# EasyEDA_ChisFlash_V0_1_Pichu.net
KiCad netlist of a schematic drawn in EasyEDA Pro
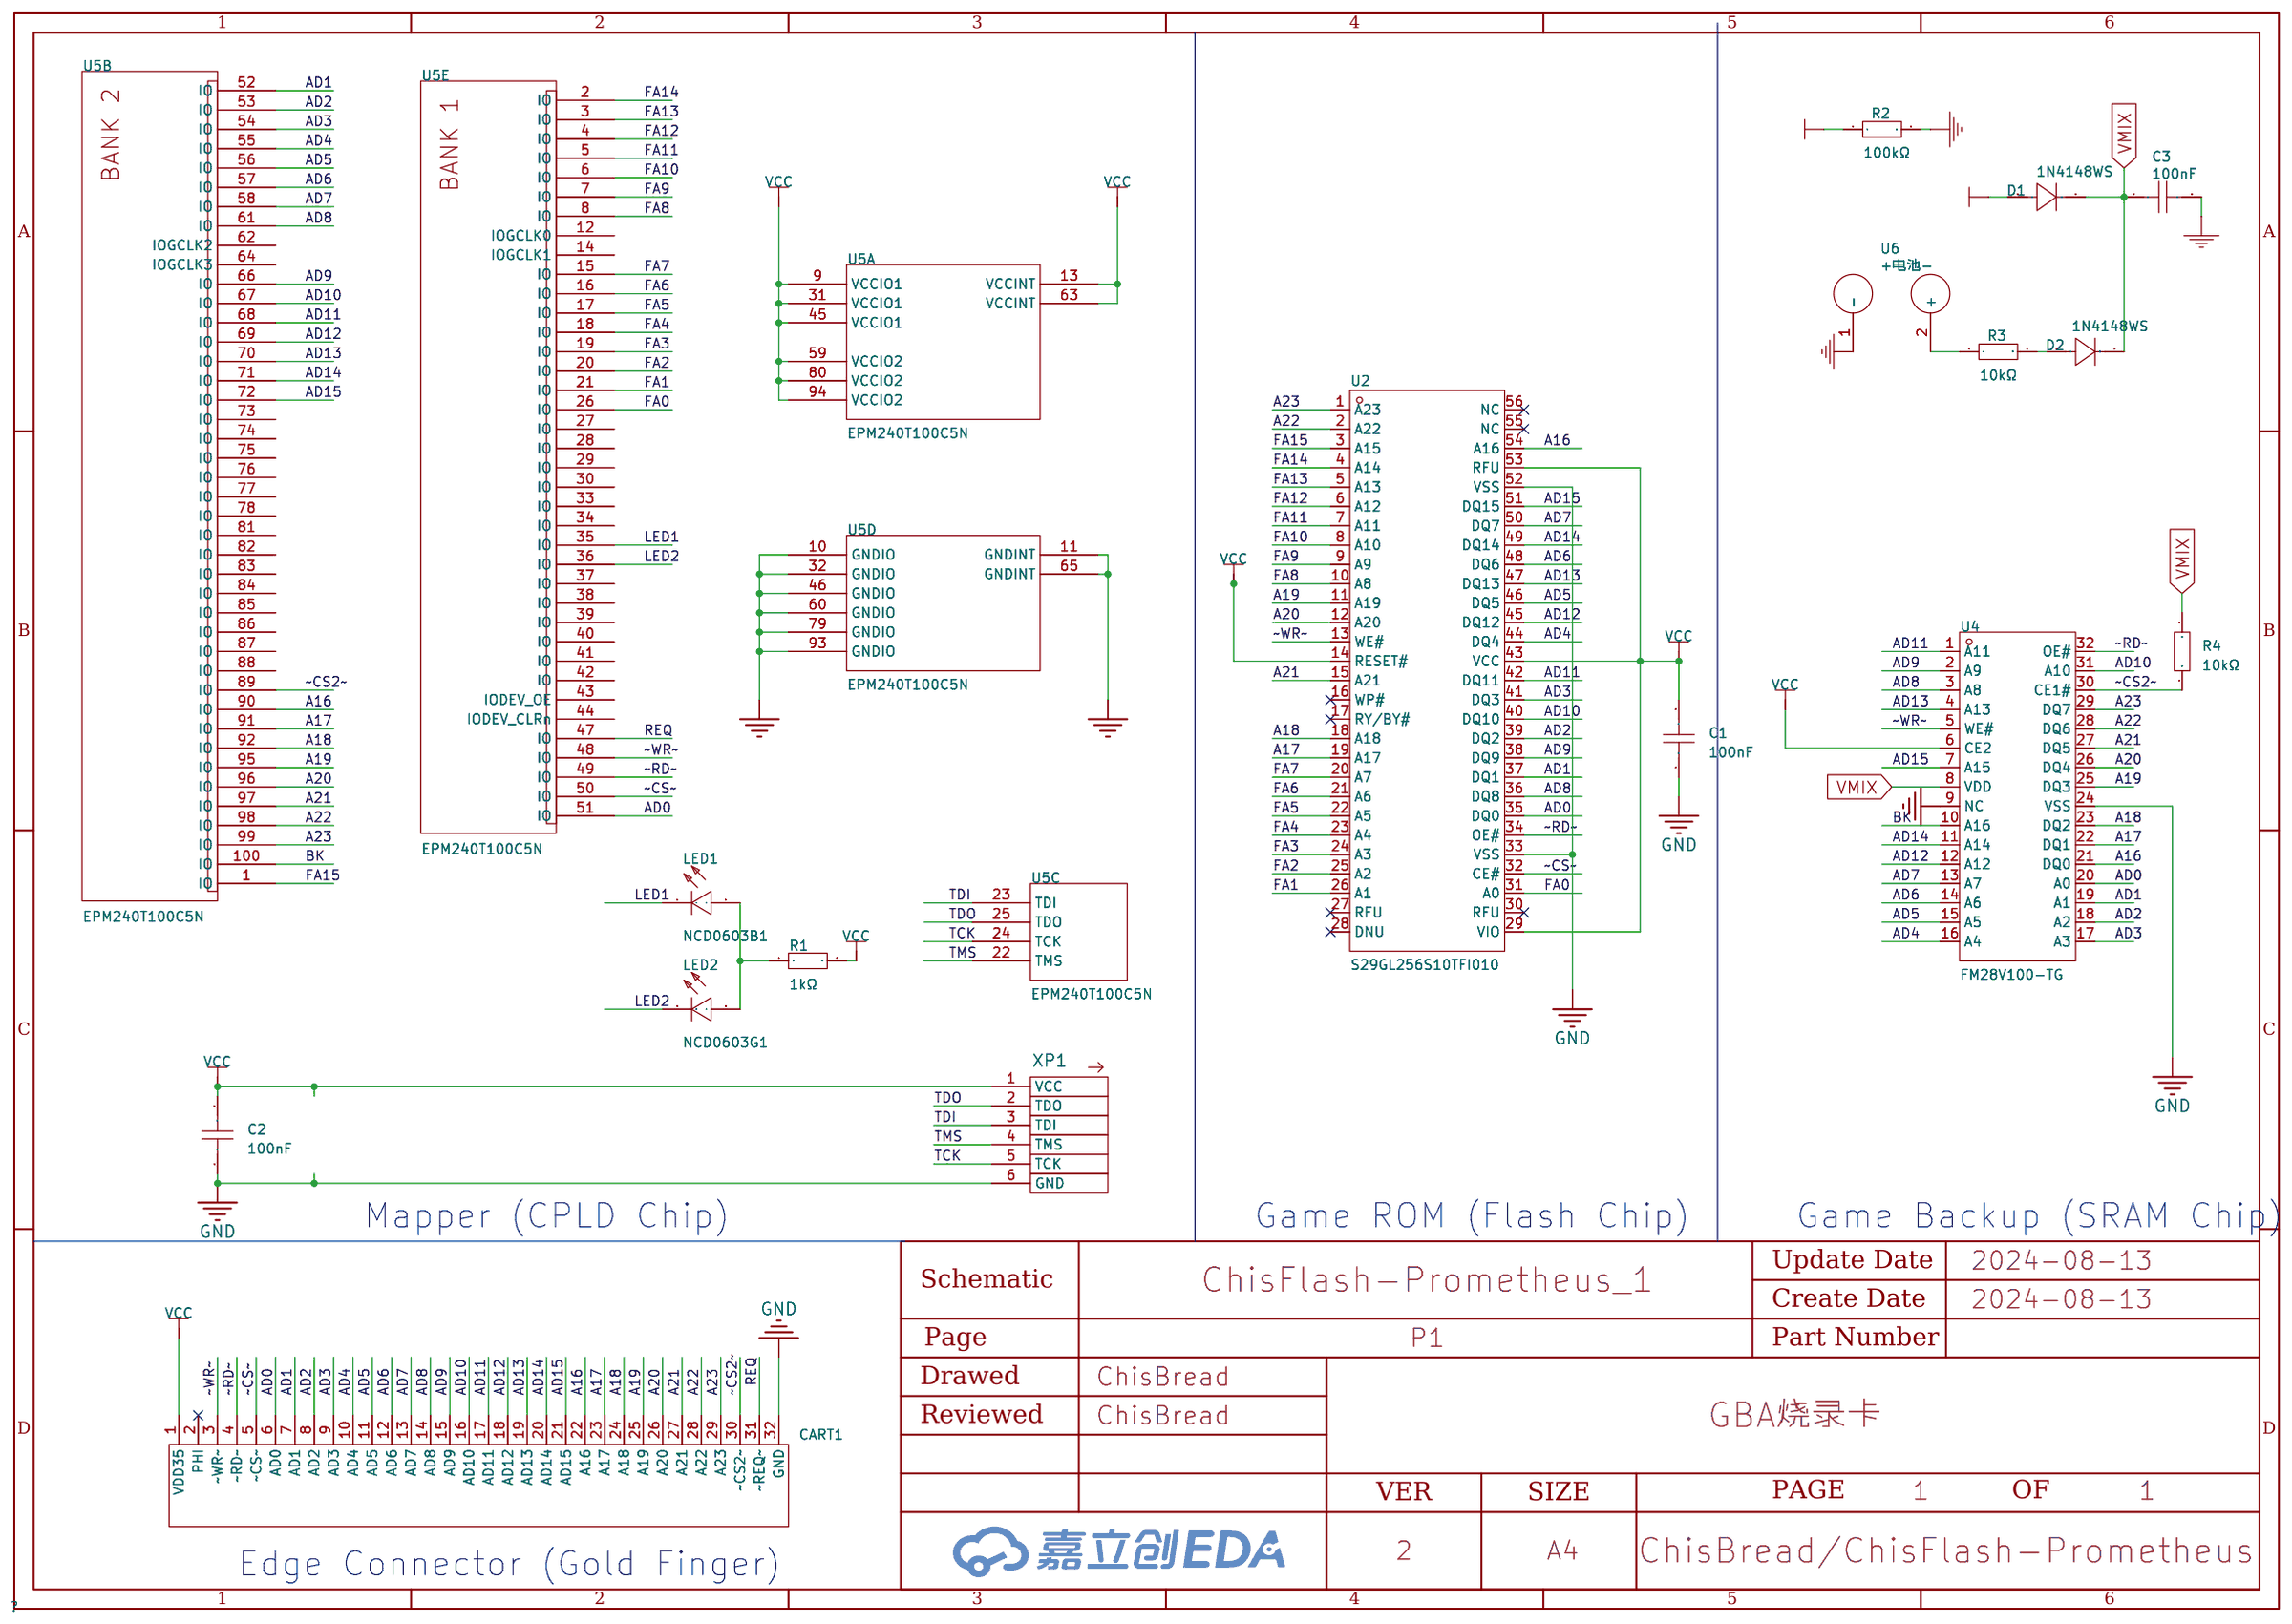
[diagram p0: schematic sheet]

(export (version "E")
  (design (tool "Eeschema 10.0.6"))
  (components
    (comp (ref "C1")
      (value "100nF")
      (footprint "easyedapro:C0603")
      (libsource (lib "easyedapro") (part "CapAcitance"))
    )
    (comp (ref "C2")
      (value "100nF")
      (footprint "easyedapro:C0603")
      (libsource (lib "easyedapro") (part "CapAcitance"))
    )
    (comp (ref "C3")
      (value "100nF")
      (footprint "easyedapro:C0603")
      (description "容值:100nF;精度:±10%;额定电压:50V;材质(温度系数):X7R;")
      (fields
        (field (name "Manufacturer Part") "CGA0603X7R104K500JT")
        (field (name "Manufacturer") "HRE(芯声)")
      )
      (libsource (lib "easyedapro") (part "CGA0603X7R104K500JT"))
    )
    (comp (ref "CART1")
      (value "~")
      (footprint "easyedapro:GBACartridge")
      (description "GBA Cartridge")
      (libsource (lib "easyedapro") (part "GBACartridge"))
    )
    (comp (ref "D1")
      (value "1N4148WS")
      (footprint "easyedapro:SOD-323_L1.8-W1.3-LS2.5-RD")
      (description "二极管配置:独立式;正向压降(Vf):1.25V@150mA;直流反向耐压(Vr):100V;平均整流电流(Io):300mA;功率:400mW;反向恢复时间(trr):8ns;")
      (fields (field (name "Manufacturer") "JSMSEMI(杰盛微)"))
      (libsource (lib "easyedapro") (part "1N4148WS_C917117"))
    )
    (comp (ref "D2")
      (value "1N4148WS")
      (footprint "easyedapro:SOD-323_L1.8-W1.3-LS2.5-RD")
      (description "二极管配置:独立式;正向压降(Vf):1.25V@150mA;直流反向耐压(Vr):100V;平均整流电流(Io):300mA;功率:400mW;反向恢复时间(trr):8ns;")
      (fields (field (name "Manufacturer") "JSMSEMI(杰盛微)"))
      (libsource (lib "easyedapro") (part "1N4148WS_C917117"))
    )
    (comp (ref "LED1")
      (value "NCD0603B1")
      (footprint "easyedapro:LED0603-RD")
      (fields (field (name "Manufacturer") "国星光电"))
      (libsource (lib "easyedapro") (part "FC-DA1608BK-470H10"))
    )
    (comp (ref "LED2")
      (value "NCD0603G1")
      (footprint "easyedapro:LED0603-RD")
      (fields (field (name "Manufacturer") "国星光电"))
      (libsource (lib "easyedapro") (part "FC-D1608UGK-520D10"))
    )
    (comp (ref "R1")
      (value "1kΩ")
      (footprint "easyedapro:R0603")
      (description "电阻类型:厚膜电阻;阻值:1kΩ;精度:±1%;功率:100mW;最大工作电压:75V;温度系数:±100ppm/°C;")
      (fields
        (field (name "Manufacturer Part") "0603WAF1001T5E")
        (field (name "Manufacturer") "UNI-ROYAL(厚声)")
      )
      (libsource (lib "easyedapro") (part "0603WAF1001T5E"))
    )
    (comp (ref "R2")
      (value "100kΩ")
      (footprint "easyedapro:R0603")
      (description "电阻类型:厚膜电阻;阻值:100kΩ;精度:±1%;功率:100mW;最大工作电压:75V;温度系数:±100ppm/°C;")
      (fields
        (field (name "Manufacturer Part") "0603WAF1003T5E")
        (field (name "Manufacturer") "UNI-ROYAL(厚声)")
      )
      (libsource (lib "easyedapro") (part "0603WAF1003T5E"))
    )
    (comp (ref "R3")
      (value "10kΩ")
      (footprint "easyedapro:R0603")
      (description "电阻类型:厚膜电阻;阻值:10kΩ;精度:±1%;功率:100mW;最大工作电压:75V;温度系数:±100ppm/°C;")
      (fields
        (field (name "Manufacturer Part") "0603WAF1002T5E")
        (field (name "Manufacturer") "UNI-ROYAL(厚声)")
      )
      (libsource (lib "easyedapro") (part "0603WAF1002T5E"))
    )
    (comp (ref "R4")
      (value "10kΩ")
      (footprint "easyedapro:R0603")
      (description "电阻类型:厚膜电阻;阻值:10kΩ;精度:±1%;功率:100mW;最大工作电压:75V;温度系数:±100ppm/°C;")
      (fields
        (field (name "Manufacturer Part") "0603WAF1002T5E")
        (field (name "Manufacturer") "UNI-ROYAL(厚声)")
      )
      (libsource (lib "easyedapro") (part "0603WAF1002T5E"))
    )
    (comp (ref "U2")
      (value "S29GL256S10TFI010")
      (footprint "easyedapro:TSOP-56_L18.4-W14.0-P0.50-LS20.0-TL")
      (fields (field (name "Manufacturer") "SPANSION(飞索)"))
      (libsource (lib "easyedapro") (part "S29GL256S10TFI010"))
    )
    (comp (ref "U4")
      (value "FM28V100-TG")
      (fields (field (name "Manufacturer") "CYPRESS(赛普拉斯)"))
      (libsource (lib "easyedapro") (part "FM28V100-TG_C2959453"))
    )
    (comp (ref "U5")
      (value "EPM240T100C5N")
      (footprint "easyedapro:TQFP-100_L14.0-W14.0-P0.50-LS16.0-BL")
      (description "类型:其它PLD;逻辑门数量:-;逻辑单元数:-;逻辑阵列块数:240;")
      (fields (field (name "Manufacturer") "Intel/Altera"))
      (libsource (lib "easyedapro") (part "EPM240T100C5N"))
    )
    (comp (ref "U6") (value "+电池-") (footprint "easyedapro:电池") (libsource (lib "easyedapro") (part "+电池-")))
    (comp (ref "XP1")
      (value "JTAG")
      (footprint "easyedapro:HDR-TH_6P-P1.27-V-M-1")
      (libsource (lib "easyedapro") (part "jtag"))
    )
  )
  (nets
    (net (code "1") (name "/A16") (class "Default")
      (node (ref "CART1") (pin "22") (pinfunction "A16_22") (pintype "input"))
      (node (ref "U2") (pin "54") (pinfunction "A16_54") (pintype "input"))
      (node (ref "U4") (pin "21") (pinfunction "DQ0_21") (pintype "unspecified"))
      (node (ref "U5") (pin "90") (pinfunction "IO_90") (pintype "bidirectional"))
    )
    (net (code "2") (name "/A17") (class "Default")
      (node (ref "CART1") (pin "23") (pinfunction "A17_23") (pintype "input"))
      (node (ref "U2") (pin "19") (pinfunction "A17_19") (pintype "input"))
      (node (ref "U4") (pin "22") (pinfunction "DQ1_22") (pintype "unspecified"))
      (node (ref "U5") (pin "91") (pinfunction "IO_91") (pintype "bidirectional"))
    )
    (net (code "3") (name "/A18") (class "Default")
      (node (ref "CART1") (pin "24") (pinfunction "A18_24") (pintype "input"))
      (node (ref "U2") (pin "18") (pinfunction "A18_18") (pintype "input"))
      (node (ref "U4") (pin "23") (pinfunction "DQ2_23") (pintype "unspecified"))
      (node (ref "U5") (pin "92") (pinfunction "IO_92") (pintype "bidirectional"))
    )
    (net (code "4") (name "/A19") (class "Default")
      (node (ref "CART1") (pin "25") (pinfunction "A19_25") (pintype "input"))
      (node (ref "U2") (pin "11") (pinfunction "A19_11") (pintype "input"))
      (node (ref "U4") (pin "25") (pinfunction "DQ3_25") (pintype "unspecified"))
      (node (ref "U5") (pin "95") (pinfunction "IO_95") (pintype "bidirectional"))
    )
    (net (code "5") (name "/A20") (class "Default")
      (node (ref "CART1") (pin "26") (pinfunction "A20_26") (pintype "input"))
      (node (ref "U2") (pin "12") (pinfunction "A20_12") (pintype "input"))
      (node (ref "U4") (pin "26") (pinfunction "DQ4_26") (pintype "unspecified"))
      (node (ref "U5") (pin "96") (pinfunction "IO_96") (pintype "bidirectional"))
    )
    (net (code "6") (name "/A21") (class "Default")
      (node (ref "CART1") (pin "27") (pinfunction "A21_27") (pintype "input"))
      (node (ref "U2") (pin "15") (pinfunction "A21_15") (pintype "input"))
      (node (ref "U4") (pin "27") (pinfunction "DQ5_27") (pintype "unspecified"))
      (node (ref "U5") (pin "97") (pinfunction "IO_97") (pintype "bidirectional"))
    )
    (net (code "7") (name "/A22") (class "Default")
      (node (ref "CART1") (pin "28") (pinfunction "A22_28") (pintype "input"))
      (node (ref "U2") (pin "2") (pinfunction "A22_2") (pintype "input"))
      (node (ref "U4") (pin "28") (pinfunction "DQ6_28") (pintype "unspecified"))
      (node (ref "U5") (pin "98") (pinfunction "IO_98") (pintype "bidirectional"))
    )
    (net (code "8") (name "/A23") (class "Default")
      (node (ref "CART1") (pin "29") (pinfunction "A23_29") (pintype "input"))
      (node (ref "U2") (pin "1") (pinfunction "A23_1") (pintype "input"))
      (node (ref "U4") (pin "29") (pinfunction "DQ7_29") (pintype "unspecified"))
      (node (ref "U5") (pin "99") (pinfunction "IO_99") (pintype "bidirectional"))
    )
    (net (code "9") (name "/AD0") (class "Default")
      (node (ref "CART1") (pin "6") (pinfunction "AD0_6") (pintype "input"))
      (node (ref "U2") (pin "35") (pinfunction "DQ0_35") (pintype "input"))
      (node (ref "U4") (pin "20") (pinfunction "A0_20") (pintype "unspecified"))
      (node (ref "U5") (pin "51") (pinfunction "IO_51") (pintype "bidirectional"))
    )
    (net (code "10") (name "/AD1") (class "Default")
      (node (ref "CART1") (pin "7") (pinfunction "AD1_7") (pintype "input"))
      (node (ref "U2") (pin "37") (pinfunction "DQ1_37") (pintype "input"))
      (node (ref "U4") (pin "19") (pinfunction "A1_19") (pintype "unspecified"))
      (node (ref "U5") (pin "52") (pinfunction "IO_52") (pintype "bidirectional"))
    )
    (net (code "11") (name "/AD2") (class "Default")
      (node (ref "CART1") (pin "8") (pinfunction "AD2_8") (pintype "input"))
      (node (ref "U2") (pin "39") (pinfunction "DQ2_39") (pintype "input"))
      (node (ref "U4") (pin "18") (pinfunction "A2_18") (pintype "unspecified"))
      (node (ref "U5") (pin "53") (pinfunction "IO_53") (pintype "bidirectional"))
    )
    (net (code "12") (name "/AD3") (class "Default")
      (node (ref "CART1") (pin "9") (pinfunction "AD3_9") (pintype "input"))
      (node (ref "U2") (pin "41") (pinfunction "DQ3_41") (pintype "input"))
      (node (ref "U4") (pin "17") (pinfunction "A3_17") (pintype "unspecified"))
      (node (ref "U5") (pin "54") (pinfunction "IO_54") (pintype "bidirectional"))
    )
    (net (code "13") (name "/AD4") (class "Default")
      (node (ref "CART1") (pin "10") (pinfunction "AD4_10") (pintype "input"))
      (node (ref "U2") (pin "44") (pinfunction "DQ4_44") (pintype "input"))
      (node (ref "U4") (pin "16") (pinfunction "A4_16") (pintype "unspecified"))
      (node (ref "U5") (pin "55") (pinfunction "IO_55") (pintype "bidirectional"))
    )
    (net (code "14") (name "/AD5") (class "Default")
      (node (ref "CART1") (pin "11") (pinfunction "AD5_11") (pintype "input"))
      (node (ref "U2") (pin "46") (pinfunction "DQ5_46") (pintype "input"))
      (node (ref "U4") (pin "15") (pinfunction "A5_15") (pintype "unspecified"))
      (node (ref "U5") (pin "56") (pinfunction "IO_56") (pintype "bidirectional"))
    )
    (net (code "15") (name "/AD6") (class "Default")
      (node (ref "CART1") (pin "12") (pinfunction "AD6_12") (pintype "input"))
      (node (ref "U2") (pin "48") (pinfunction "DQ6_48") (pintype "input"))
      (node (ref "U4") (pin "14") (pinfunction "A6_14") (pintype "unspecified"))
      (node (ref "U5") (pin "57") (pinfunction "IO_57") (pintype "bidirectional"))
    )
    (net (code "16") (name "/AD7") (class "Default")
      (node (ref "CART1") (pin "13") (pinfunction "AD7_13") (pintype "input"))
      (node (ref "U2") (pin "50") (pinfunction "DQ7_50") (pintype "input"))
      (node (ref "U4") (pin "13") (pinfunction "A7_13") (pintype "unspecified"))
      (node (ref "U5") (pin "58") (pinfunction "IO_58") (pintype "bidirectional"))
    )
    (net (code "17") (name "/AD8") (class "Default")
      (node (ref "CART1") (pin "14") (pinfunction "AD8_14") (pintype "input"))
      (node (ref "U2") (pin "36") (pinfunction "DQ8_36") (pintype "input"))
      (node (ref "U4") (pin "3") (pinfunction "A8_3") (pintype "unspecified"))
      (node (ref "U5") (pin "61") (pinfunction "IO_61") (pintype "bidirectional"))
    )
    (net (code "18") (name "/AD9") (class "Default")
      (node (ref "CART1") (pin "15") (pinfunction "AD9_15") (pintype "input"))
      (node (ref "U2") (pin "38") (pinfunction "DQ9_38") (pintype "input"))
      (node (ref "U4") (pin "2") (pinfunction "A9_2") (pintype "unspecified"))
      (node (ref "U5") (pin "66") (pinfunction "IO_66") (pintype "bidirectional"))
    )
    (net (code "19") (name "/AD10") (class "Default")
      (node (ref "CART1") (pin "16") (pinfunction "AD10_16") (pintype "input"))
      (node (ref "U2") (pin "40") (pinfunction "DQ10_40") (pintype "input"))
      (node (ref "U4") (pin "31") (pinfunction "A10_31") (pintype "unspecified"))
      (node (ref "U5") (pin "67") (pinfunction "IO_67") (pintype "bidirectional"))
    )
    (net (code "20") (name "/AD11") (class "Default")
      (node (ref "CART1") (pin "17") (pinfunction "AD11_17") (pintype "input"))
      (node (ref "U2") (pin "42") (pinfunction "DQ11_42") (pintype "input"))
      (node (ref "U4") (pin "1") (pinfunction "A11_1") (pintype "unspecified"))
      (node (ref "U5") (pin "68") (pinfunction "IO_68") (pintype "bidirectional"))
    )
    (net (code "21") (name "/AD12") (class "Default")
      (node (ref "CART1") (pin "18") (pinfunction "AD12_18") (pintype "input"))
      (node (ref "U2") (pin "45") (pinfunction "DQ12_45") (pintype "input"))
      (node (ref "U4") (pin "12") (pinfunction "A12_12") (pintype "unspecified"))
      (node (ref "U5") (pin "69") (pinfunction "IO_69") (pintype "bidirectional"))
    )
    (net (code "22") (name "/AD13") (class "Default")
      (node (ref "CART1") (pin "19") (pinfunction "AD13_19") (pintype "input"))
      (node (ref "U2") (pin "47") (pinfunction "DQ13_47") (pintype "input"))
      (node (ref "U4") (pin "4") (pinfunction "A13_4") (pintype "unspecified"))
      (node (ref "U5") (pin "70") (pinfunction "IO_70") (pintype "bidirectional"))
    )
    (net (code "23") (name "/AD14") (class "Default")
      (node (ref "CART1") (pin "20") (pinfunction "AD14_20") (pintype "input"))
      (node (ref "U2") (pin "49") (pinfunction "DQ14_49") (pintype "input"))
      (node (ref "U4") (pin "11") (pinfunction "A14_11") (pintype "unspecified"))
      (node (ref "U5") (pin "71") (pinfunction "IO_71") (pintype "bidirectional"))
    )
    (net (code "24") (name "/AD15") (class "Default")
      (node (ref "CART1") (pin "21") (pinfunction "AD15_21") (pintype "input"))
      (node (ref "U2") (pin "51") (pinfunction "DQ15_51") (pintype "input"))
      (node (ref "U4") (pin "7") (pinfunction "A15_7") (pintype "unspecified"))
      (node (ref "U5") (pin "72") (pinfunction "IO_72") (pintype "bidirectional"))
    )
    (net (code "25") (name "/BK") (class "Default")
      (node (ref "U4") (pin "10") (pinfunction "A16_10") (pintype "unspecified"))
      (node (ref "U5") (pin "100") (pinfunction "IO_100") (pintype "bidirectional"))
    )
    (net (code "26") (name "/FA0") (class "Default")
      (node (ref "U2") (pin "31") (pinfunction "A0_31") (pintype "input"))
      (node (ref "U5") (pin "26") (pinfunction "IO_26") (pintype "bidirectional"))
    )
    (net (code "27") (name "/FA1") (class "Default")
      (node (ref "U2") (pin "26") (pinfunction "A1_26") (pintype "input"))
      (node (ref "U5") (pin "21") (pinfunction "IO_21") (pintype "bidirectional"))
    )
    (net (code "28") (name "/FA2") (class "Default")
      (node (ref "U2") (pin "25") (pinfunction "A2_25") (pintype "input"))
      (node (ref "U5") (pin "20") (pinfunction "IO_20") (pintype "bidirectional"))
    )
    (net (code "29") (name "/FA3") (class "Default")
      (node (ref "U2") (pin "24") (pinfunction "A3_24") (pintype "input"))
      (node (ref "U5") (pin "19") (pinfunction "IO_19") (pintype "bidirectional"))
    )
    (net (code "30") (name "/FA4") (class "Default")
      (node (ref "U2") (pin "23") (pinfunction "A4_23") (pintype "input"))
      (node (ref "U5") (pin "18") (pinfunction "IO_18") (pintype "bidirectional"))
    )
    (net (code "31") (name "/FA5") (class "Default")
      (node (ref "U2") (pin "22") (pinfunction "A5_22") (pintype "input"))
      (node (ref "U5") (pin "17") (pinfunction "IO_17") (pintype "bidirectional"))
    )
    (net (code "32") (name "/FA6") (class "Default")
      (node (ref "U2") (pin "21") (pinfunction "A6_21") (pintype "input"))
      (node (ref "U5") (pin "16") (pinfunction "IO_16") (pintype "bidirectional"))
    )
    (net (code "33") (name "/FA7") (class "Default")
      (node (ref "U2") (pin "20") (pinfunction "A7_20") (pintype "input"))
      (node (ref "U5") (pin "15") (pinfunction "IO_15") (pintype "bidirectional"))
    )
    (net (code "34") (name "/FA8") (class "Default")
      (node (ref "U2") (pin "10") (pinfunction "A8_10") (pintype "input"))
      (node (ref "U5") (pin "8") (pinfunction "IO_8") (pintype "bidirectional"))
    )
    (net (code "35") (name "/FA9") (class "Default")
      (node (ref "U2") (pin "9") (pinfunction "A9_9") (pintype "input"))
      (node (ref "U5") (pin "7") (pinfunction "IO_7") (pintype "bidirectional"))
    )
    (net (code "36") (name "/FA10") (class "Default")
      (node (ref "U2") (pin "8") (pinfunction "A10_8") (pintype "input"))
      (node (ref "U5") (pin "6") (pinfunction "IO_6") (pintype "bidirectional"))
    )
    (net (code "37") (name "/FA11") (class "Default")
      (node (ref "U2") (pin "7") (pinfunction "A11_7") (pintype "input"))
      (node (ref "U5") (pin "5") (pinfunction "IO_5") (pintype "bidirectional"))
    )
    (net (code "38") (name "/FA12") (class "Default")
      (node (ref "U2") (pin "6") (pinfunction "A12_6") (pintype "input"))
      (node (ref "U5") (pin "4") (pinfunction "IO_4") (pintype "bidirectional"))
    )
    (net (code "39") (name "/FA13") (class "Default")
      (node (ref "U2") (pin "5") (pinfunction "A13_5") (pintype "input"))
      (node (ref "U5") (pin "3") (pinfunction "IO_3") (pintype "bidirectional"))
    )
    (net (code "40") (name "/FA14") (class "Default")
      (node (ref "U2") (pin "4") (pinfunction "A14_4") (pintype "input"))
      (node (ref "U5") (pin "2") (pinfunction "IO_2") (pintype "bidirectional"))
    )
    (net (code "41") (name "/FA15") (class "Default")
      (node (ref "U2") (pin "3") (pinfunction "A15_3") (pintype "input"))
      (node (ref "U5") (pin "1") (pinfunction "IO_1") (pintype "bidirectional"))
    )
    (net (code "42") (name "/LED1") (class "Default")
      (node (ref "LED1") (pin "1") (pinfunction "-_1") (pintype "input"))
      (node (ref "U5") (pin "35") (pinfunction "IO_35") (pintype "bidirectional"))
    )
    (net (code "43") (name "/LED2") (class "Default")
      (node (ref "LED2") (pin "1") (pinfunction "K_1") (pintype "input"))
      (node (ref "U5") (pin "36") (pinfunction "IO_36") (pintype "bidirectional"))
    )
    (net (code "44") (name "/REQ") (class "Default")
      (node (ref "CART1") (pin "31") (pinfunction "~REQ~_31") (pintype "input"))
      (node (ref "U5") (pin "47") (pinfunction "IO_47") (pintype "bidirectional"))
    )
    (net (code "45") (name "/TCK") (class "Default")
      (node (ref "U5") (pin "24") (pinfunction "TCK_24") (pintype "unspecified"))
      (node (ref "XP1") (pin "5") (pinfunction "TCK_5") (pintype "input"))
    )
    (net (code "46") (name "/TDI") (class "Default")
      (node (ref "U5") (pin "23") (pinfunction "TDI_23") (pintype "unspecified"))
      (node (ref "XP1") (pin "3") (pinfunction "TDI_3") (pintype "output"))
    )
    (net (code "47") (name "/TDO") (class "Default")
      (node (ref "U5") (pin "25") (pinfunction "TDO_25") (pintype "output"))
      (node (ref "XP1") (pin "2") (pinfunction "TDO_2") (pintype "output"))
    )
    (net (code "48") (name "/TMS") (class "Default")
      (node (ref "U5") (pin "22") (pinfunction "TMS_22") (pintype "unspecified"))
      (node (ref "XP1") (pin "4") (pinfunction "TMS_4") (pintype "output"))
    )
    (net (code "49") (name "/~CS2~") (class "Default")
      (node (ref "CART1") (pin "30") (pinfunction "~CS2~_30") (pintype "input"))
      (node (ref "R4") (pin "1") (pinfunction "1_1") (pintype "input"))
      (node (ref "U4") (pin "30") (pinfunction "CE1#_30") (pintype "unspecified"))
      (node (ref "U5") (pin "89") (pinfunction "IO_89") (pintype "bidirectional"))
    )
    (net (code "50") (name "/~CS~") (class "Default")
      (node (ref "CART1") (pin "5") (pinfunction "~CS~_5") (pintype "input"))
      (node (ref "U2") (pin "32") (pinfunction "CE#_32") (pintype "input"))
      (node (ref "U5") (pin "50") (pinfunction "IO_50") (pintype "bidirectional"))
    )
    (net (code "51") (name "/~RD~") (class "Default")
      (node (ref "CART1") (pin "4") (pinfunction "~RD~_4") (pintype "input"))
      (node (ref "U2") (pin "34") (pinfunction "OE#_34") (pintype "input"))
      (node (ref "U4") (pin "32") (pinfunction "OE#_32") (pintype "unspecified"))
      (node (ref "U5") (pin "49") (pinfunction "IO_49") (pintype "bidirectional"))
    )
    (net (code "52") (name "/~WR~") (class "Default")
      (node (ref "CART1") (pin "3") (pinfunction "~WR~_3") (pintype "input"))
      (node (ref "U2") (pin "13") (pinfunction "WE#_13") (pintype "input"))
      (node (ref "U4") (pin "5") (pinfunction "WE#_5") (pintype "unspecified"))
      (node (ref "U5") (pin "48") (pinfunction "IO_48") (pintype "bidirectional"))
    )
    (net (code "53") (name "GND") (class "Default")
      (node (ref "C1") (pin "1") (pinfunction "1_1") (pintype "input"))
      (node (ref "C2") (pin "1") (pinfunction "1_1") (pintype "input"))
      (node (ref "C3") (pin "2") (pinfunction "2_2") (pintype "unspecified"))
      (node (ref "CART1") (pin "32") (pinfunction "GND_32") (pintype "input"))
      (node (ref "R2") (pin "2") (pinfunction "2_2") (pintype "input"))
      (node (ref "U2") (pin "33") (pinfunction "VSS_33") (pintype "input"))
      (node (ref "U2") (pin "52") (pinfunction "VSS_52") (pintype "input"))
      (node (ref "U4") (pin "24") (pinfunction "VSS_24") (pintype "unspecified"))
      (node (ref "U4") (pin "9") (pinfunction "NC_9") (pintype "unspecified"))
      (node (ref "U5") (pin "10") (pinfunction "GNDIO_10") (pintype "unspecified"))
      (node (ref "U5") (pin "11") (pinfunction "GNDINT_11") (pintype "unspecified"))
      (node (ref "U5") (pin "32") (pinfunction "GNDIO_32") (pintype "unspecified"))
      (node (ref "U5") (pin "46") (pinfunction "GNDIO_46") (pintype "unspecified"))
      (node (ref "U5") (pin "60") (pinfunction "GNDIO_60") (pintype "unspecified"))
      (node (ref "U5") (pin "65") (pinfunction "GNDINT_65") (pintype "unspecified"))
      (node (ref "U5") (pin "79") (pinfunction "GNDIO_79") (pintype "unspecified"))
      (node (ref "U5") (pin "93") (pinfunction "GNDIO_93") (pintype "unspecified"))
      (node (ref "U6") (pin "1") (pinfunction "-_1") (pintype "unspecified"))
      (node (ref "XP1") (pin "6") (pinfunction "GND_6") (pintype "input"))
    )
    (net (code "54") (name "Net-(D2-A)") (class "Default")
      (node (ref "D2") (pin "2") (pinfunction "A_2") (pintype "unspecified"))
      (node (ref "R3") (pin "2") (pinfunction "2_2") (pintype "input"))
    )
    (net (code "55") (name "Net-(LED1-+)") (class "Default")
      (node (ref "LED1") (pin "2") (pinfunction "+_2") (pintype "input"))
      (node (ref "LED2") (pin "2") (pinfunction "A_2") (pintype "input"))
      (node (ref "R1") (pin "1") (pinfunction "1_1") (pintype "input"))
    )
    (net (code "56") (name "Net-(U6-+)") (class "Default")
      (node (ref "R3") (pin "1") (pinfunction "1_1") (pintype "input"))
      (node (ref "U6") (pin "2") (pinfunction "+_2") (pintype "unspecified"))
    )
    (net (code "57") (name "VCC") (class "Default")
      (node (ref "C1") (pin "2") (pinfunction "2_2") (pintype "input"))
      (node (ref "C2") (pin "2") (pinfunction "2_2") (pintype "input"))
      (node (ref "CART1") (pin "1") (pinfunction "VDD35_1") (pintype "input"))
      (node (ref "D1") (pin "2") (pinfunction "A_2") (pintype "unspecified"))
      (node (ref "R1") (pin "2") (pinfunction "2_2") (pintype "input"))
      (node (ref "R2") (pin "1") (pinfunction "1_1") (pintype "input"))
      (node (ref "U2") (pin "14") (pinfunction "RESET#_14") (pintype "input"))
      (node (ref "U2") (pin "29") (pinfunction "VIO_29") (pintype "input"))
      (node (ref "U2") (pin "43") (pinfunction "VCC_43") (pintype "input"))
      (node (ref "U2") (pin "53") (pinfunction "RFU_53") (pintype "input"))
      (node (ref "U4") (pin "6") (pinfunction "CE2_6") (pintype "unspecified"))
      (node (ref "U5") (pin "13") (pinfunction "VCCINT_13") (pintype "unspecified"))
      (node (ref "U5") (pin "31") (pinfunction "VCCIO1_31") (pintype "unspecified"))
      (node (ref "U5") (pin "45") (pinfunction "VCCIO1_45") (pintype "unspecified"))
      (node (ref "U5") (pin "59") (pinfunction "VCCIO2_59") (pintype "unspecified"))
      (node (ref "U5") (pin "63") (pinfunction "VCCINT_63") (pintype "unspecified"))
      (node (ref "U5") (pin "80") (pinfunction "VCCIO2_80") (pintype "unspecified"))
      (node (ref "U5") (pin "9") (pinfunction "VCCIO1_9") (pintype "unspecified"))
      (node (ref "U5") (pin "94") (pinfunction "VCCIO2_94") (pintype "unspecified"))
      (node (ref "XP1") (pin "1") (pinfunction "VCC_1") (pintype "output"))
    )
    (net (code "58") (name "VMIX") (class "Default")
      (node (ref "C3") (pin "1") (pinfunction "1_1") (pintype "unspecified"))
      (node (ref "D1") (pin "1") (pinfunction "C_1") (pintype "unspecified"))
      (node (ref "D2") (pin "1") (pinfunction "C_1") (pintype "unspecified"))
      (node (ref "R4") (pin "2") (pinfunction "2_2") (pintype "input"))
      (node (ref "U4") (pin "8") (pinfunction "VDD_8") (pintype "unspecified"))
    )
    (net (code "59") (name "unconnected-(CART1-PHI-Pad2)") (class "Default")
      (node (ref "CART1") (pin "2") (pinfunction "PHI_2") (pintype "input+no_connect"))
    )
    (net (code "60") (name "unconnected-(U2-DNU-Pad28)") (class "Default")
      (node (ref "U2") (pin "28") (pinfunction "DNU_28") (pintype "input+no_connect"))
    )
    (net (code "61") (name "unconnected-(U2-NC-Pad55)") (class "Default")
      (node (ref "U2") (pin "55") (pinfunction "NC_55") (pintype "input+no_connect"))
    )
    (net (code "62") (name "unconnected-(U2-NC-Pad56)") (class "Default")
      (node (ref "U2") (pin "56") (pinfunction "NC_56") (pintype "input+no_connect"))
    )
    (net (code "63") (name "unconnected-(U2-RFU-Pad27)") (class "Default")
      (node (ref "U2") (pin "27") (pinfunction "RFU_27") (pintype "input+no_connect"))
    )
    (net (code "64") (name "unconnected-(U2-RFU-Pad30)") (class "Default")
      (node (ref "U2") (pin "30") (pinfunction "RFU_30") (pintype "input+no_connect"))
    )
    (net (code "65") (name "unconnected-(U2-RY{slash}BY#-Pad17)") (class "Default")
      (node (ref "U2") (pin "17") (pinfunction "RY/BY#_17") (pintype "input+no_connect"))
    )
    (net (code "66") (name "unconnected-(U2-WP#-Pad16)") (class "Default")
      (node (ref "U2") (pin "16") (pinfunction "WP#_16") (pintype "input+no_connect"))
    )
    (net (code "67") (name "unconnected-(U5B-IO-Pad73)") (class "Default")
      (node (ref "U5") (pin "73") (pinfunction "IO_73") (pintype "bidirectional"))
    )
    (net (code "68") (name "unconnected-(U5B-IO-Pad74)") (class "Default")
      (node (ref "U5") (pin "74") (pinfunction "IO_74") (pintype "bidirectional"))
    )
    (net (code "69") (name "unconnected-(U5B-IO-Pad75)") (class "Default")
      (node (ref "U5") (pin "75") (pinfunction "IO_75") (pintype "bidirectional"))
    )
    (net (code "70") (name "unconnected-(U5B-IO-Pad76)") (class "Default")
      (node (ref "U5") (pin "76") (pinfunction "IO_76") (pintype "bidirectional"))
    )
    (net (code "71") (name "unconnected-(U5B-IO-Pad77)") (class "Default")
      (node (ref "U5") (pin "77") (pinfunction "IO_77") (pintype "bidirectional"))
    )
    (net (code "72") (name "unconnected-(U5B-IO-Pad78)") (class "Default")
      (node (ref "U5") (pin "78") (pinfunction "IO_78") (pintype "bidirectional"))
    )
    (net (code "73") (name "unconnected-(U5B-IO-Pad81)") (class "Default")
      (node (ref "U5") (pin "81") (pinfunction "IO_81") (pintype "bidirectional"))
    )
    (net (code "74") (name "unconnected-(U5B-IO-Pad82)") (class "Default")
      (node (ref "U5") (pin "82") (pinfunction "IO_82") (pintype "bidirectional"))
    )
    (net (code "75") (name "unconnected-(U5B-IO-Pad83)") (class "Default")
      (node (ref "U5") (pin "83") (pinfunction "IO_83") (pintype "bidirectional"))
    )
    (net (code "76") (name "unconnected-(U5B-IO-Pad84)") (class "Default")
      (node (ref "U5") (pin "84") (pinfunction "IO_84") (pintype "bidirectional"))
    )
    (net (code "77") (name "unconnected-(U5B-IO-Pad85)") (class "Default")
      (node (ref "U5") (pin "85") (pinfunction "IO_85") (pintype "bidirectional"))
    )
    (net (code "78") (name "unconnected-(U5B-IO-Pad86)") (class "Default")
      (node (ref "U5") (pin "86") (pinfunction "IO_86") (pintype "bidirectional"))
    )
    (net (code "79") (name "unconnected-(U5B-IO-Pad87)") (class "Default")
      (node (ref "U5") (pin "87") (pinfunction "IO_87") (pintype "bidirectional"))
    )
    (net (code "80") (name "unconnected-(U5B-IO-Pad88)") (class "Default")
      (node (ref "U5") (pin "88") (pinfunction "IO_88") (pintype "bidirectional"))
    )
    (net (code "81") (name "unconnected-(U5B-IOGCLK2-Pad62)") (class "Default")
      (node (ref "U5") (pin "62") (pinfunction "IOGCLK2_62") (pintype "bidirectional"))
    )
    (net (code "82") (name "unconnected-(U5B-IOGCLK3-Pad64)") (class "Default")
      (node (ref "U5") (pin "64") (pinfunction "IOGCLK3_64") (pintype "bidirectional"))
    )
    (net (code "83") (name "unconnected-(U5E-IO-Pad27)") (class "Default")
      (node (ref "U5") (pin "27") (pinfunction "IO_27") (pintype "bidirectional"))
    )
    (net (code "84") (name "unconnected-(U5E-IO-Pad28)") (class "Default")
      (node (ref "U5") (pin "28") (pinfunction "IO_28") (pintype "bidirectional"))
    )
    (net (code "85") (name "unconnected-(U5E-IO-Pad29)") (class "Default")
      (node (ref "U5") (pin "29") (pinfunction "IO_29") (pintype "bidirectional"))
    )
    (net (code "86") (name "unconnected-(U5E-IO-Pad30)") (class "Default")
      (node (ref "U5") (pin "30") (pinfunction "IO_30") (pintype "bidirectional"))
    )
    (net (code "87") (name "unconnected-(U5E-IO-Pad33)") (class "Default")
      (node (ref "U5") (pin "33") (pinfunction "IO_33") (pintype "bidirectional"))
    )
    (net (code "88") (name "unconnected-(U5E-IO-Pad34)") (class "Default")
      (node (ref "U5") (pin "34") (pinfunction "IO_34") (pintype "bidirectional"))
    )
    (net (code "89") (name "unconnected-(U5E-IO-Pad37)") (class "Default")
      (node (ref "U5") (pin "37") (pinfunction "IO_37") (pintype "bidirectional"))
    )
    (net (code "90") (name "unconnected-(U5E-IO-Pad38)") (class "Default")
      (node (ref "U5") (pin "38") (pinfunction "IO_38") (pintype "bidirectional"))
    )
    (net (code "91") (name "unconnected-(U5E-IO-Pad39)") (class "Default")
      (node (ref "U5") (pin "39") (pinfunction "IO_39") (pintype "bidirectional"))
    )
    (net (code "92") (name "unconnected-(U5E-IO-Pad40)") (class "Default")
      (node (ref "U5") (pin "40") (pinfunction "IO_40") (pintype "bidirectional"))
    )
    (net (code "93") (name "unconnected-(U5E-IO-Pad41)") (class "Default")
      (node (ref "U5") (pin "41") (pinfunction "IO_41") (pintype "bidirectional"))
    )
    (net (code "94") (name "unconnected-(U5E-IO-Pad42)") (class "Default")
      (node (ref "U5") (pin "42") (pinfunction "IO_42") (pintype "bidirectional"))
    )
    (net (code "95") (name "unconnected-(U5E-IODEV_CLRn-Pad44)") (class "Default")
      (node (ref "U5") (pin "44") (pinfunction "IODEV_CLRn_44") (pintype "bidirectional"))
    )
    (net (code "96") (name "unconnected-(U5E-IODEV_OE-Pad43)") (class "Default")
      (node (ref "U5") (pin "43") (pinfunction "IODEV_OE_43") (pintype "bidirectional"))
    )
    (net (code "97") (name "unconnected-(U5E-IOGCLK0-Pad12)") (class "Default")
      (node (ref "U5") (pin "12") (pinfunction "IOGCLK0_12") (pintype "bidirectional"))
    )
    (net (code "98") (name "unconnected-(U5E-IOGCLK1-Pad14)") (class "Default")
      (node (ref "U5") (pin "14") (pinfunction "IOGCLK1_14") (pintype "bidirectional"))
    )
  )
)
